# MSPM0G3107.net
KiCad netlist of a schematic drawn in EAGLE
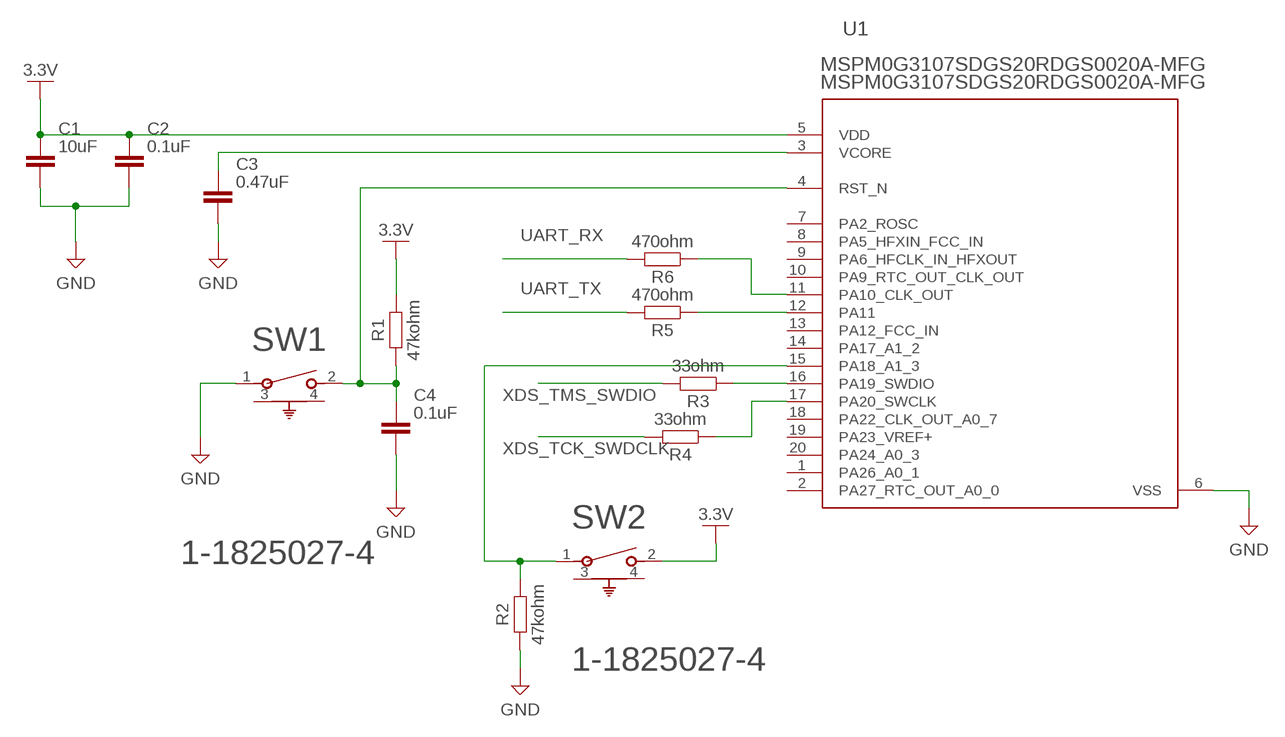
[diagram p0: schematic, sheet 1]

(export (version "E")
  (design (tool "Eeschema 10.0.6"))
  (components
    (comp (ref "C1")
      (value "10uF")
      (footprint "eagle-import:CAPC2012X110")
      (libsource (lib "eagle-import") (part "CCHIP-0805(2012-METRIC)_"))
    )
    (comp (ref "C2")
      (value "0.1uF")
      (footprint "eagle-import:CAPC2012X110")
      (libsource (lib "eagle-import") (part "CCHIP-0805(2012-METRIC)_"))
    )
    (comp (ref "C3")
      (value "0.47uF")
      (footprint "eagle-import:CAPC2012X110")
      (libsource (lib "eagle-import") (part "CCHIP-0805(2012-METRIC)_"))
    )
    (comp (ref "C4")
      (value "0.1uF")
      (footprint "eagle-import:CAPC2012X110")
      (libsource (lib "eagle-import") (part "CCHIP-0805(2012-METRIC)_"))
    )
    (comp (ref "R1")
      (value "47kohm")
      (footprint "eagle-import:RESC1608X60")
      (libsource (lib "eagle-import") (part "RCHIP-0603(1608-METRIC)_"))
    )
    (comp (ref "R2")
      (value "47kohm")
      (footprint "eagle-import:RESC1608X60")
      (libsource (lib "eagle-import") (part "RCHIP-0603(1608-METRIC)_"))
    )
    (comp (ref "R3")
      (value "33ohm")
      (footprint "eagle-import:RESC1608X60")
      (libsource (lib "eagle-import") (part "RCHIP-0603(1608-METRIC)_"))
    )
    (comp (ref "R4")
      (value "33ohm")
      (footprint "eagle-import:RESC1608X60")
      (libsource (lib "eagle-import") (part "RCHIP-0603(1608-METRIC)_"))
    )
    (comp (ref "R5")
      (value "470ohm")
      (footprint "eagle-import:RESC1608X60")
      (libsource (lib "eagle-import") (part "RCHIP-0603(1608-METRIC)_"))
    )
    (comp (ref "R6")
      (value "470ohm")
      (footprint "eagle-import:RESC1608X60")
      (libsource (lib "eagle-import") (part "RCHIP-0603(1608-METRIC)_"))
    )
    (comp (ref "SW1")
      (value "1-1825027-4")
      (footprint "eagle-import:SW2_1825027-E")
      (fields (field (name "COPYRIGHT") "Copyright (C) 2016 Accelerated Designs. All rights reserved"))
      (libsource (lib "eagle-import") (part "1-1825027-4"))
    )
    (comp (ref "SW2")
      (value "1-1825027-4")
      (footprint "eagle-import:SW2_1825027-E")
      (fields (field (name "COPYRIGHT") "Copyright (C) 2016 Accelerated Designs. All rights reserved"))
      (libsource (lib "eagle-import") (part "1-1825027-4"))
    )
    (comp (ref "U1")
      (value "MSPM0G3107SDGS20RDGS0020A-MFG")
      (footprint "eagle-import:DGS0020A-MFG")
      (fields
        (field (name "MANUFACTURER_PART_NUMBER") "MSPM0G3107SDGS20R")
        (field (name "COPYRIGHT") "Copyright (C) 2025 Ultra Librarian. All rights reserved.")
      )
      (libsource (lib "eagle-import") (part "MSPM0G3107SDGS20RDGS0020A-MFG"))
    )
  )
  (nets
    (net (code "1") (name "/UART_RX") (class "Default")
      (node (ref "R6") (pin "2") (pinfunction "2_2") (pintype "passive"))
    )
    (net (code "2") (name "/UART_TX") (class "Default")
      (node (ref "R5") (pin "2") (pinfunction "2_2") (pintype "passive"))
    )
    (net (code "3") (name "/XDS_TCK_SWDCLK") (class "Default")
      (node (ref "R4") (pin "2") (pinfunction "2_2") (pintype "passive"))
    )
    (net (code "4") (name "/XDS_TMS_SWDIO") (class "Default")
      (node (ref "R3") (pin "2") (pinfunction "2_2") (pintype "passive"))
    )
    (net (code "5") (name "3.3V") (class "Default")
      (node (ref "C1") (pin "1") (pinfunction "1_1") (pintype "passive"))
      (node (ref "C2") (pin "1") (pinfunction "1_1") (pintype "passive"))
      (node (ref "R1") (pin "2") (pinfunction "2_2") (pintype "passive"))
      (node (ref "SW2") (pin "2") (pinfunction "2_2") (pintype "passive"))
      (node (ref "U1") (pin "5") (pinfunction "VDD_5") (pintype "power_in"))
    )
    (net (code "6") (name "GND") (class "Default")
      (node (ref "C1") (pin "2") (pinfunction "2_2") (pintype "passive"))
      (node (ref "C2") (pin "2") (pinfunction "2_2") (pintype "passive"))
      (node (ref "C3") (pin "2") (pinfunction "2_2") (pintype "passive"))
      (node (ref "C4") (pin "2") (pinfunction "2_2") (pintype "passive"))
      (node (ref "R2") (pin "1") (pinfunction "1_1") (pintype "passive"))
      (node (ref "SW1") (pin "1") (pinfunction "1_1") (pintype "passive"))
      (node (ref "U1") (pin "6") (pinfunction "VSS_6") (pintype "power_in"))
    )
    (net (code "7") (name "Net-(U1-PA10_CLK_OUT)") (class "Default")
      (node (ref "R6") (pin "1") (pinfunction "1_1") (pintype "passive"))
      (node (ref "U1") (pin "11") (pinfunction "PA10_CLK_OUT_11") (pintype "bidirectional"))
    )
    (net (code "8") (name "Net-(U1-PA11)") (class "Default")
      (node (ref "R5") (pin "1") (pinfunction "1_1") (pintype "passive"))
      (node (ref "U1") (pin "12") (pinfunction "PA11_12") (pintype "bidirectional"))
    )
    (net (code "9") (name "Net-(U1-PA18_A1_3)") (class "Default")
      (node (ref "R2") (pin "2") (pinfunction "2_2") (pintype "passive"))
      (node (ref "SW2") (pin "1") (pinfunction "1_1") (pintype "passive"))
      (node (ref "U1") (pin "15") (pinfunction "PA18_A1_3_15") (pintype "bidirectional"))
    )
    (net (code "10") (name "Net-(U1-PA19_SWDIO)") (class "Default")
      (node (ref "R3") (pin "1") (pinfunction "1_1") (pintype "passive"))
      (node (ref "U1") (pin "16") (pinfunction "PA19_SWDIO_16") (pintype "bidirectional"))
    )
    (net (code "11") (name "Net-(U1-PA20_SWCLK)") (class "Default")
      (node (ref "R4") (pin "1") (pinfunction "1_1") (pintype "passive"))
      (node (ref "U1") (pin "17") (pinfunction "PA20_SWCLK_17") (pintype "bidirectional"))
    )
    (net (code "12") (name "Net-(U1-RST_N)") (class "Default")
      (node (ref "C4") (pin "1") (pinfunction "1_1") (pintype "passive"))
      (node (ref "R1") (pin "1") (pinfunction "1_1") (pintype "passive"))
      (node (ref "SW1") (pin "2") (pinfunction "2_2") (pintype "passive"))
      (node (ref "U1") (pin "4") (pinfunction "RST_N_4") (pintype "input"))
    )
    (net (code "13") (name "Net-(U1-VCORE)") (class "Default")
      (node (ref "C3") (pin "1") (pinfunction "1_1") (pintype "passive"))
      (node (ref "U1") (pin "3") (pinfunction "VCORE_3") (pintype "power_in"))
    )
    (net (code "14") (name "unconnected-(SW1-Pad3)") (class "Default")
      (node (ref "SW1") (pin "3") (pinfunction "3_3") (pintype "passive"))
    )
    (net (code "15") (name "unconnected-(SW1-Pad4)") (class "Default")
      (node (ref "SW1") (pin "4") (pinfunction "4_4") (pintype "passive"))
    )
    (net (code "16") (name "unconnected-(SW2-Pad3)") (class "Default")
      (node (ref "SW2") (pin "3") (pinfunction "3_3") (pintype "passive"))
    )
    (net (code "17") (name "unconnected-(SW2-Pad4)") (class "Default")
      (node (ref "SW2") (pin "4") (pinfunction "4_4") (pintype "passive"))
    )
    (net (code "18") (name "unconnected-(U1-PA2_ROSC-Pad7)") (class "Default")
      (node (ref "U1") (pin "7") (pinfunction "PA2_ROSC_7") (pintype "bidirectional"))
    )
    (net (code "19") (name "unconnected-(U1-PA5_HFXIN_FCC_IN-Pad8)") (class "Default")
      (node (ref "U1") (pin "8") (pinfunction "PA5_HFXIN_FCC_IN_8") (pintype "bidirectional"))
    )
    (net (code "20") (name "unconnected-(U1-PA6_HFCLK_IN_HFXOUT-Pad9)") (class "Default")
      (node (ref "U1") (pin "9") (pinfunction "PA6_HFCLK_IN_HFXOUT_9") (pintype "bidirectional"))
    )
    (net (code "21") (name "unconnected-(U1-PA9_RTC_OUT_CLK_OUT-Pad10)") (class "Default")
      (node (ref "U1") (pin "10") (pinfunction "PA9_RTC_OUT_CLK_OUT_10") (pintype "bidirectional"))
    )
    (net (code "22") (name "unconnected-(U1-PA12_FCC_IN-Pad13)") (class "Default")
      (node (ref "U1") (pin "13") (pinfunction "PA12_FCC_IN_13") (pintype "bidirectional"))
    )
    (net (code "23") (name "unconnected-(U1-PA17_A1_2-Pad14)") (class "Default")
      (node (ref "U1") (pin "14") (pinfunction "PA17_A1_2_14") (pintype "bidirectional"))
    )
    (net (code "24") (name "unconnected-(U1-PA22_CLK_OUT_A0_7-Pad18)") (class "Default")
      (node (ref "U1") (pin "18") (pinfunction "PA22_CLK_OUT_A0_7_18") (pintype "bidirectional"))
    )
    (net (code "25") (name "unconnected-(U1-PA23_VREF+-Pad19)") (class "Default")
      (node (ref "U1") (pin "19") (pinfunction "PA23_VREF+_19") (pintype "bidirectional"))
    )
    (net (code "26") (name "unconnected-(U1-PA24_A0_3-Pad20)") (class "Default")
      (node (ref "U1") (pin "20") (pinfunction "PA24_A0_3_20") (pintype "bidirectional"))
    )
    (net (code "27") (name "unconnected-(U1-PA26_A0_1-Pad1)") (class "Default")
      (node (ref "U1") (pin "1") (pinfunction "PA26_A0_1_1") (pintype "bidirectional"))
    )
    (net (code "28") (name "unconnected-(U1-PA27_RTC_OUT_A0_0-Pad2)") (class "Default")
      (node (ref "U1") (pin "2") (pinfunction "PA27_RTC_OUT_A0_0_2") (pintype "bidirectional"))
    )
  )
)
